# biolab_rev2.net
KiCad netlist of a schematic drawn in Altium Designer
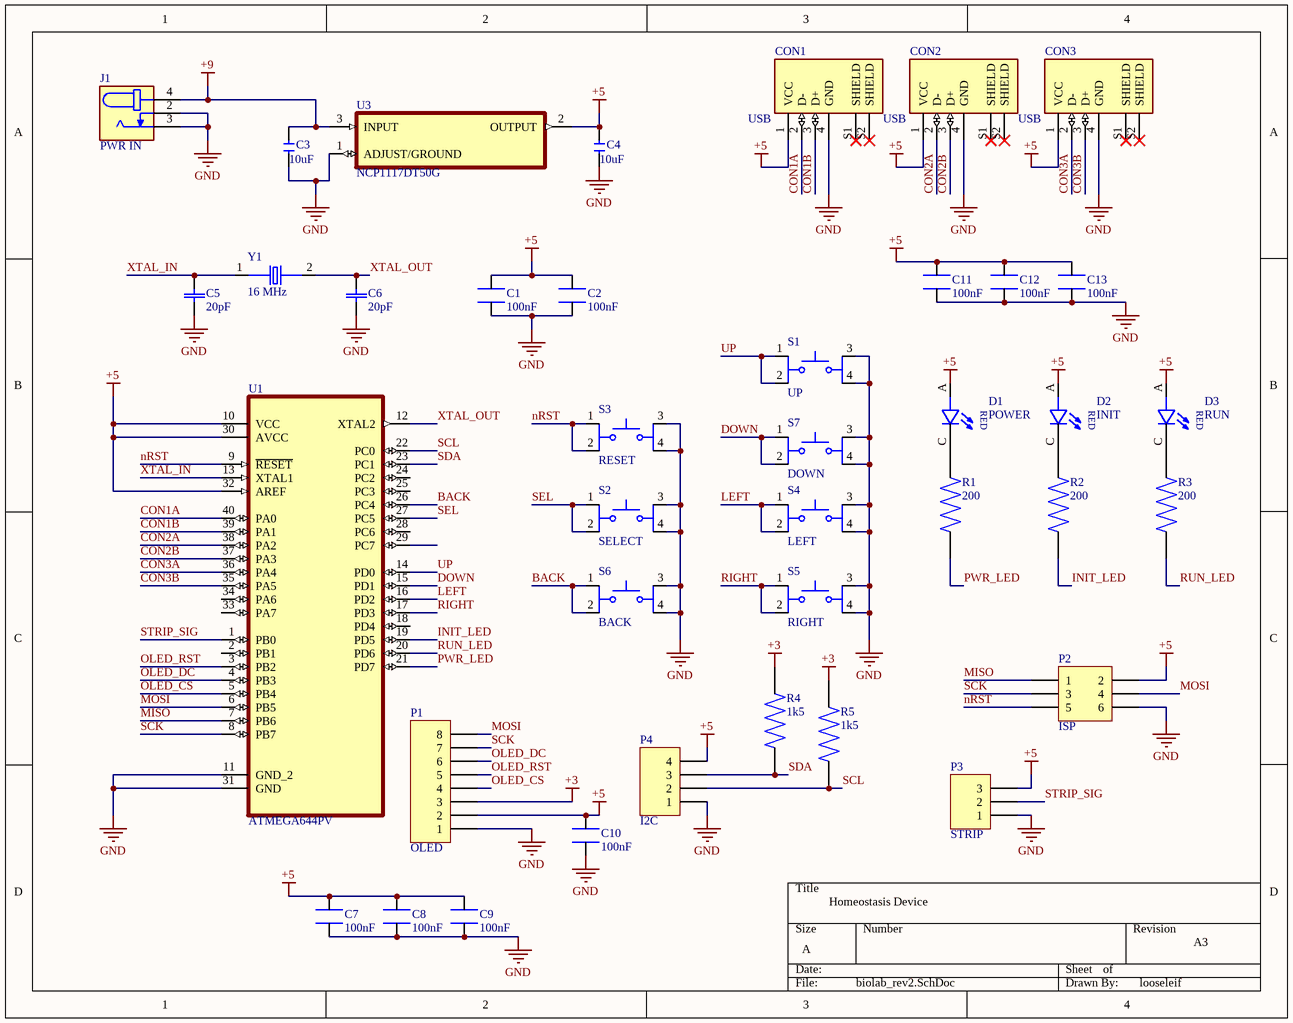
[diagram p0: biolab_rev2.SchDoc]

(export (version "E")
  (design (tool "Eeschema 10.0.6"))
  (components
    (comp (ref "C1")
      (value "100nF")
      (footprint "WCAP-CSST_885382206004")
      (fields
        (field (name "MP") "885382206004")
        (field (name "MF") "{'manufacturer': u'Wurth Electronics Inc'}")
      )
      (libsource (lib "biolab_interface") (part "885382206004"))
    )
    (comp (ref "C2")
      (value "100nF")
      (footprint "WCAP-CSST_885382206004")
      (fields
        (field (name "MP") "885382206004")
        (field (name "MF") "{'manufacturer': u'Wurth Electronics Inc'}")
      )
      (libsource (lib "biolab_interface") (part "885382206004"))
    )
    (comp (ref "C3")
      (value "10uF")
      (footprint "C0603")
      (description "302010103")
      (fields
        (field (name "MP") "CERAMIC-10UF-10V-10%-X5R(0603)")
        (field (name "MF") "{'manufacturer': u'Yageo'}")
      )
      (libsource (lib "SnapEDA_Library") (part "CERAMIC-10UF-10V-10%-X5R(0603)"))
    )
    (comp (ref "C4")
      (value "10uF")
      (footprint "C0603")
      (description "302010103")
      (fields
        (field (name "MP") "CERAMIC-10UF-10V-10%-X5R(0603)")
        (field (name "MF") "{'manufacturer': u'Yageo'}")
      )
      (libsource (lib "SnapEDA_Library") (part "CERAMIC-10UF-10V-10%-X5R(0603)"))
    )
    (comp (ref "C5")
      (value "20pF")
      (footprint "CAPC1608X85N")
      (description "CAPACITOR, 0603")
      (fields (field (name "MP") "C0603C200J5GACTU") (field (name "MF") "{'manufacturer': u'KEMET'}"))
      (libsource (lib "SnapEDA_Library") (part "C0603C200J5GACTU"))
    )
    (comp (ref "C6")
      (value "20pF")
      (footprint "CAPC1608X85N")
      (description "CAPACITOR, 0603")
      (fields (field (name "MP") "C0603C200J5GACTU") (field (name "MF") "{'manufacturer': u'KEMET'}"))
      (libsource (lib "SnapEDA_Library") (part "C0603C200J5GACTU"))
    )
    (comp (ref "C7")
      (value "100nF")
      (footprint "WCAP-CSST_885382206004")
      (fields
        (field (name "MP") "885382206004")
        (field (name "MF") "{'manufacturer': u'Wurth Electronics Inc'}")
      )
      (libsource (lib "biolab_interface") (part "885382206004"))
    )
    (comp (ref "C8")
      (value "100nF")
      (footprint "WCAP-CSST_885382206004")
      (fields
        (field (name "MP") "885382206004")
        (field (name "MF") "{'manufacturer': u'Wurth Electronics Inc'}")
      )
      (libsource (lib "biolab_interface") (part "885382206004"))
    )
    (comp (ref "C9")
      (value "100nF")
      (footprint "WCAP-CSST_885382206004")
      (fields
        (field (name "MP") "885382206004")
        (field (name "MF") "{'manufacturer': u'Wurth Electronics Inc'}")
      )
      (libsource (lib "biolab_interface") (part "885382206004"))
    )
    (comp (ref "C10")
      (value "100nF")
      (footprint "WCAP-CSST_885382206004")
      (fields
        (field (name "MP") "885382206004")
        (field (name "MF") "{'manufacturer': u'Wurth Electronics Inc'}")
      )
      (libsource (lib "biolab_interface") (part "885382206004"))
    )
    (comp (ref "C11")
      (value "100nF")
      (footprint "WCAP-CSST_885382206004")
      (fields
        (field (name "MP") "885382206004")
        (field (name "MF") "{'manufacturer': u'Wurth Electronics Inc'}")
      )
      (libsource (lib "biolab_interface") (part "885382206004"))
    )
    (comp (ref "C12")
      (value "100nF")
      (footprint "WCAP-CSST_885382206004")
      (fields
        (field (name "MP") "885382206004")
        (field (name "MF") "{'manufacturer': u'Wurth Electronics Inc'}")
      )
      (libsource (lib "biolab_interface") (part "885382206004"))
    )
    (comp (ref "C13")
      (value "100nF")
      (footprint "WCAP-CSST_885382206004")
      (fields
        (field (name "MP") "885382206004")
        (field (name "MF") "{'manufacturer': u'Wurth Electronics Inc'}")
      )
      (libsource (lib "biolab_interface") (part "885382206004"))
    )
    (comp (ref "CON1")
      (value "USB")
      (footprint "GCT_USB1130-15-A_REVA")
      (fields
        (field (name "MP") "USB1130-15-A_REVA")
        (field (name "MF") "{'manufacturer': u'Global Connector Technology'}")
      )
      (libsource (lib "SnapEDA_Library") (part "USB1130-15-A_REVA"))
    )
    (comp (ref "CON2")
      (value "USB")
      (footprint "GCT_USB1130-15-A_REVA")
      (fields
        (field (name "MP") "USB1130-15-A_REVA")
        (field (name "MF") "{'manufacturer': u'Global Connector Technology'}")
      )
      (libsource (lib "SnapEDA_Library") (part "USB1130-15-A_REVA"))
    )
    (comp (ref "CON3")
      (value "USB")
      (footprint "GCT_USB1130-15-A_REVA")
      (fields
        (field (name "MP") "USB1130-15-A_REVA")
        (field (name "MF") "{'manufacturer': u'Global Connector Technology'}")
      )
      (libsource (lib "SnapEDA_Library") (part "USB1130-15-A_REVA"))
    )
    (comp (ref "D1")
      (value "POWER")
      (footprint "LED_7012X1")
      (description "Red LED Indication - Discrete 1.7V 0805 (2012 Metric)")
      (fields (field (name "MP") "7012X1") (field (name "MF") "{'manufacturer': u'Visual'}"))
      (libsource (lib "SnapEDA_Library") (part "7012X1"))
    )
    (comp (ref "D2")
      (value "INIT")
      (footprint "LED_7012X1")
      (description "Red LED Indication - Discrete 1.7V 0805 (2012 Metric)")
      (fields (field (name "MP") "7012X1") (field (name "MF") "{'manufacturer': u'Visual'}"))
      (libsource (lib "SnapEDA_Library") (part "7012X1"))
    )
    (comp (ref "D3")
      (value "RUN")
      (footprint "LED_7012X1")
      (description "Red LED Indication - Discrete 1.7V 0805 (2012 Metric)")
      (fields (field (name "MP") "7012X1") (field (name "MF") "{'manufacturer': u'Visual'}"))
      (libsource (lib "SnapEDA_Library") (part "7012X1"))
    )
    (comp (ref "J1")
      (value "PWR IN")
      (footprint "NINIGI_DC-005")
      (description "DC Jack")
      (fields (field (name "MP") "DC-005") (field (name "MF") "{'manufacturer': u'Best Inc.'}"))
      (libsource (lib "SnapEDA_Library") (part "DC-005"))
    )
    (comp (ref "P1")
      (value "OLED")
      (footprint "HDR1X8")
      (description "Header, 8-Pin")
      (fields (field (name "PUBLISHER") "Altium Limited"))
      (libsource (lib "Miscellaneous Connectors") (part "Header 8"))
    )
    (comp (ref "P2")
      (value "ISP")
      (footprint "HDR2X3")
      (description "Header, 3-Pin, Dual row")
      (fields (field (name "PUBLISHER") "Altium Limited"))
      (libsource (lib "Miscellaneous Connectors") (part "Header 3X2"))
    )
    (comp (ref "P3")
      (value "STRIP")
      (footprint "HDR1X3H")
      (description "Header, 3-Pin, Right Angle")
      (fields (field (name "PUBLISHER") "Altium Limited"))
      (libsource (lib "Miscellaneous Connectors") (part "Header 3H"))
    )
    (comp (ref "P4")
      (value "I2C")
      (footprint "HDR1X4H")
      (description "Header, 4-Pin, Right Angle")
      (fields (field (name "PUBLISHER") "Altium Limited"))
      (libsource (lib "Miscellaneous Connectors") (part "Header 4H"))
    )
    (comp (ref "R1")
      (value "200")
      (footprint "RESC1608X55N")
      (fields (field (name "MP") "SR0603JR-07200RL") (field (name "MF") "{'manufacturer': u'Yageo'}"))
      (libsource (lib "biolab_interface") (part "SR0603JR-07200RL"))
    )
    (comp (ref "R2")
      (value "200")
      (footprint "RESC1608X55N")
      (fields (field (name "MP") "SR0603JR-07200RL") (field (name "MF") "{'manufacturer': u'Yageo'}"))
      (libsource (lib "biolab_interface") (part "SR0603JR-07200RL"))
    )
    (comp (ref "R3")
      (value "200")
      (footprint "RESC1608X55N")
      (fields (field (name "MP") "SR0603JR-07200RL") (field (name "MF") "{'manufacturer': u'Yageo'}"))
      (libsource (lib "biolab_interface") (part "SR0603JR-07200RL"))
    )
    (comp (ref "R4")
      (value "1k5")
      (footprint "RESC1508X55N")
      (fields (field (name "MP") "TNPW06031K50BXEN") (field (name "MF") "{'manufacturer': u'Vishay'}"))
      (libsource (lib "biolab_interface") (part "TNPW06031K50BXEN"))
    )
    (comp (ref "R5")
      (value "1k5")
      (footprint "RESC1508X55N")
      (fields (field (name "MP") "TNPW06031K50BXEN") (field (name "MF") "{'manufacturer': u'Vishay'}"))
      (libsource (lib "biolab_interface") (part "TNPW06031K50BXEN"))
    )
    (comp (ref "S1")
      (value "UP")
      (footprint "SW_TL3301AF160QG")
      (fields (field (name "MP") "TL3301AF160QG") (field (name "MF") "{'manufacturer': u'E-Switch'}"))
      (libsource (lib "biolab_interface") (part "TL3301AF160QG"))
    )
    (comp (ref "S2")
      (value "SELECT")
      (footprint "SW_TL3301AF160QG")
      (fields (field (name "MP") "TL3301AF160QG") (field (name "MF") "{'manufacturer': u'E-Switch'}"))
      (libsource (lib "biolab_interface") (part "TL3301AF160QG"))
    )
    (comp (ref "S3")
      (value "RESET")
      (footprint "SW_TL3301AF160QG")
      (fields (field (name "MP") "TL3301AF160QG") (field (name "MF") "{'manufacturer': u'E-Switch'}"))
      (libsource (lib "biolab_interface") (part "TL3301AF160QG"))
    )
    (comp (ref "S4")
      (value "LEFT")
      (footprint "SW_TL3301AF160QG")
      (fields (field (name "MP") "TL3301AF160QG") (field (name "MF") "{'manufacturer': u'E-Switch'}"))
      (libsource (lib "biolab_interface") (part "TL3301AF160QG"))
    )
    (comp (ref "S5")
      (value "RIGHT")
      (footprint "SW_TL3301AF160QG")
      (fields (field (name "MP") "TL3301AF160QG") (field (name "MF") "{'manufacturer': u'E-Switch'}"))
      (libsource (lib "biolab_interface") (part "TL3301AF160QG"))
    )
    (comp (ref "S6")
      (value "BACK")
      (footprint "SW_TL3301AF160QG")
      (fields (field (name "MP") "TL3301AF160QG") (field (name "MF") "{'manufacturer': u'E-Switch'}"))
      (libsource (lib "biolab_interface") (part "TL3301AF160QG"))
    )
    (comp (ref "S7")
      (value "DOWN")
      (footprint "SW_TL3301AF160QG")
      (fields (field (name "MP") "TL3301AF160QG") (field (name "MF") "{'manufacturer': u'E-Switch'}"))
      (libsource (lib "biolab_interface") (part "TL3301AF160QG"))
    )
    (comp (ref "U1")
      (value "ATMEGA644PV")
      (footprint "DIP254P1524X483-40")
      (description "8-bit Microcontroller with In-System Programmable  Flash")
      (fields
        (field (name "MP") "ATMEGA644PV-10PU")
        (field (name "MF") "{'manufacturer': u'Microchip Technology'}")
      )
      (libsource (lib "SnapEDA_Library") (part "ATMEGA644PV-10PU"))
    )
    (comp (ref "U3")
      (value "NCP1117DT50G")
      (footprint "DPAK229P990X238-4N")
      (fields (field (name "MF") "{'manufacturer': u'ON Semiconductor'}"))
      (libsource (lib "SnapEDA_Library") (part "NCP1117DT50G"))
    )
    (comp (ref "Y1")
      (value "16 MHz")
      (footprint "XTAL_FOXSDLF/160-20")
      (description "Crystal 16MHz 20pF 2-Pin HC-49/SD")
      (fields (field (name "MP") "FOXSDLF/160-20") (field (name "MF") "{'manufacturer': u'Fox Electronics'}"))
      (libsource (lib "SnapEDA_Library") (part "FOXSDLF/160-20"))
    )
  )
  (nets
    (net (code "1") (name "+3") (class "Default")
      (node (ref "P1") (pin "3") (pinfunction "3_3") (pintype "passive"))
      (node (ref "R4") (pin "2") (pinfunction "2_2") (pintype "passive"))
      (node (ref "R5") (pin "2") (pinfunction "2_2") (pintype "passive"))
    )
    (net (code "2") (name "+5") (class "Default")
      (node (ref "C1") (pin "2") (pinfunction "2_2") (pintype "passive"))
      (node (ref "C10") (pin "2") (pinfunction "2_2") (pintype "passive"))
      (node (ref "C11") (pin "2") (pinfunction "2_2") (pintype "passive"))
      (node (ref "C12") (pin "2") (pinfunction "2_2") (pintype "passive"))
      (node (ref "C13") (pin "2") (pinfunction "2_2") (pintype "passive"))
      (node (ref "C2") (pin "2") (pinfunction "2_2") (pintype "passive"))
      (node (ref "C4") (pin "2") (pinfunction "2_2") (pintype "passive"))
      (node (ref "C7") (pin "2") (pinfunction "2_2") (pintype "passive"))
      (node (ref "C8") (pin "2") (pinfunction "2_2") (pintype "passive"))
      (node (ref "C9") (pin "2") (pinfunction "2_2") (pintype "passive"))
      (node (ref "CON1") (pin "1") (pinfunction "VCC_1") (pintype "power_in"))
      (node (ref "CON2") (pin "1") (pinfunction "VCC_1") (pintype "power_in"))
      (node (ref "CON3") (pin "1") (pinfunction "VCC_1") (pintype "power_in"))
      (node (ref "D1") (pin "A") (pinfunction "A_A") (pintype "passive"))
      (node (ref "D2") (pin "A") (pinfunction "A_A") (pintype "passive"))
      (node (ref "D3") (pin "A") (pinfunction "A_A") (pintype "passive"))
      (node (ref "P1") (pin "2") (pinfunction "2_2") (pintype "passive"))
      (node (ref "P2") (pin "2") (pinfunction "2_2") (pintype "passive"))
      (node (ref "P3") (pin "3") (pinfunction "3_3") (pintype "passive"))
      (node (ref "P4") (pin "4") (pinfunction "4_4") (pintype "passive"))
      (node (ref "U1") (pin "10") (pinfunction "VCC_10") (pintype "power_in"))
      (node (ref "U1") (pin "30") (pinfunction "AVCC_30") (pintype "power_in"))
      (node (ref "U1") (pin "32") (pinfunction "AREF_32") (pintype "input"))
      (node (ref "U3") (pin "2") (pinfunction "OUTPUT_2") (pintype "output"))
    )
    (net (code "3") (name "+9") (class "Default")
      (node (ref "C3") (pin "2") (pinfunction "2_2") (pintype "passive"))
      (node (ref "J1") (pin "4") (pinfunction "2_4") (pintype "passive"))
      (node (ref "U3") (pin "3") (pinfunction "INPUT_3") (pintype "input"))
    )
    (net (code "4") (name "/BACK") (class "Default")
      (node (ref "S6") (pin "1") (pinfunction "1_1") (pintype "passive"))
      (node (ref "S6") (pin "2") (pinfunction "2_2") (pintype "passive"))
      (node (ref "U1") (pin "26") (pinfunction "PC4_26") (pintype "bidirectional"))
    )
    (net (code "5") (name "/CON1A") (class "Default")
      (node (ref "CON1") (pin "2") (pinfunction "D-_2") (pintype "bidirectional"))
      (node (ref "U1") (pin "40") (pinfunction "PA0_40") (pintype "bidirectional"))
    )
    (net (code "6") (name "/CON1B") (class "Default")
      (node (ref "CON1") (pin "3") (pinfunction "D+_3") (pintype "bidirectional"))
      (node (ref "U1") (pin "39") (pinfunction "PA1_39") (pintype "bidirectional"))
    )
    (net (code "7") (name "/CON2A") (class "Default")
      (node (ref "CON2") (pin "2") (pinfunction "D-_2") (pintype "bidirectional"))
      (node (ref "U1") (pin "38") (pinfunction "PA2_38") (pintype "bidirectional"))
    )
    (net (code "8") (name "/CON2B") (class "Default")
      (node (ref "CON2") (pin "3") (pinfunction "D+_3") (pintype "bidirectional"))
      (node (ref "U1") (pin "37") (pinfunction "PA3_37") (pintype "bidirectional"))
    )
    (net (code "9") (name "/CON3A") (class "Default")
      (node (ref "CON3") (pin "2") (pinfunction "D-_2") (pintype "bidirectional"))
      (node (ref "U1") (pin "36") (pinfunction "PA4_36") (pintype "bidirectional"))
    )
    (net (code "10") (name "/CON3B") (class "Default")
      (node (ref "CON3") (pin "3") (pinfunction "D+_3") (pintype "bidirectional"))
      (node (ref "U1") (pin "35") (pinfunction "PA5_35") (pintype "bidirectional"))
    )
    (net (code "11") (name "/DOWN") (class "Default")
      (node (ref "S7") (pin "1") (pinfunction "1_1") (pintype "passive"))
      (node (ref "S7") (pin "2") (pinfunction "2_2") (pintype "passive"))
      (node (ref "U1") (pin "15") (pinfunction "PD1_15") (pintype "bidirectional"))
    )
    (net (code "12") (name "/INIT_LED") (class "Default")
      (node (ref "R2") (pin "1") (pinfunction "1_1") (pintype "passive"))
      (node (ref "U1") (pin "19") (pinfunction "PD5_19") (pintype "bidirectional"))
    )
    (net (code "13") (name "/LEFT") (class "Default")
      (node (ref "S4") (pin "1") (pinfunction "1_1") (pintype "passive"))
      (node (ref "S4") (pin "2") (pinfunction "2_2") (pintype "passive"))
      (node (ref "U1") (pin "16") (pinfunction "PD2_16") (pintype "bidirectional"))
    )
    (net (code "14") (name "/MISO") (class "Default")
      (node (ref "P2") (pin "1") (pinfunction "1_1") (pintype "passive"))
      (node (ref "U1") (pin "7") (pinfunction "PB6_7") (pintype "bidirectional"))
    )
    (net (code "15") (name "/MOSI") (class "Default")
      (node (ref "P1") (pin "8") (pinfunction "8_8") (pintype "passive"))
      (node (ref "P2") (pin "4") (pinfunction "4_4") (pintype "passive"))
      (node (ref "U1") (pin "6") (pinfunction "PB5_6") (pintype "bidirectional"))
    )
    (net (code "16") (name "/OLED_CS") (class "Default")
      (node (ref "P1") (pin "4") (pinfunction "4_4") (pintype "passive"))
      (node (ref "U1") (pin "5") (pinfunction "PB4_5") (pintype "bidirectional"))
    )
    (net (code "17") (name "/OLED_DC") (class "Default")
      (node (ref "P1") (pin "6") (pinfunction "6_6") (pintype "passive"))
      (node (ref "U1") (pin "4") (pinfunction "PB3_4") (pintype "bidirectional"))
    )
    (net (code "18") (name "/OLED_RST") (class "Default")
      (node (ref "P1") (pin "5") (pinfunction "5_5") (pintype "passive"))
      (node (ref "U1") (pin "3") (pinfunction "PB2_3") (pintype "bidirectional"))
    )
    (net (code "19") (name "/PWR_LED") (class "Default")
      (node (ref "R1") (pin "1") (pinfunction "1_1") (pintype "passive"))
      (node (ref "U1") (pin "21") (pinfunction "PD7_21") (pintype "bidirectional"))
    )
    (net (code "20") (name "/RIGHT") (class "Default")
      (node (ref "S5") (pin "1") (pinfunction "1_1") (pintype "passive"))
      (node (ref "S5") (pin "2") (pinfunction "2_2") (pintype "passive"))
      (node (ref "U1") (pin "17") (pinfunction "PD3_17") (pintype "bidirectional"))
    )
    (net (code "21") (name "/RUN_LED") (class "Default")
      (node (ref "R3") (pin "1") (pinfunction "1_1") (pintype "passive"))
      (node (ref "U1") (pin "20") (pinfunction "PD6_20") (pintype "bidirectional"))
    )
    (net (code "22") (name "/SCK") (class "Default")
      (node (ref "P1") (pin "7") (pinfunction "7_7") (pintype "passive"))
      (node (ref "P2") (pin "3") (pinfunction "3_3") (pintype "passive"))
      (node (ref "U1") (pin "8") (pinfunction "PB7_8") (pintype "bidirectional"))
    )
    (net (code "23") (name "/SCL") (class "Default")
      (node (ref "P4") (pin "2") (pinfunction "2_2") (pintype "passive"))
      (node (ref "R5") (pin "1") (pinfunction "1_1") (pintype "passive"))
      (node (ref "U1") (pin "22") (pinfunction "PC0_22") (pintype "bidirectional"))
    )
    (net (code "24") (name "/SDA") (class "Default")
      (node (ref "P4") (pin "3") (pinfunction "3_3") (pintype "passive"))
      (node (ref "R4") (pin "1") (pinfunction "1_1") (pintype "passive"))
      (node (ref "U1") (pin "23") (pinfunction "PC1_23") (pintype "bidirectional"))
    )
    (net (code "25") (name "/SEL") (class "Default")
      (node (ref "S2") (pin "1") (pinfunction "1_1") (pintype "passive"))
      (node (ref "S2") (pin "2") (pinfunction "2_2") (pintype "passive"))
      (node (ref "U1") (pin "27") (pinfunction "PC5_27") (pintype "bidirectional"))
    )
    (net (code "26") (name "/STRIP_SIG") (class "Default")
      (node (ref "P3") (pin "2") (pinfunction "2_2") (pintype "passive"))
      (node (ref "U1") (pin "1") (pinfunction "PB0_1") (pintype "bidirectional"))
    )
    (net (code "27") (name "/UP") (class "Default")
      (node (ref "S1") (pin "1") (pinfunction "1_1") (pintype "passive"))
      (node (ref "S1") (pin "2") (pinfunction "2_2") (pintype "passive"))
      (node (ref "U1") (pin "14") (pinfunction "PD0_14") (pintype "bidirectional"))
    )
    (net (code "28") (name "/XTAL_IN") (class "Default")
      (node (ref "C5") (pin "2") (pinfunction "C2_2") (pintype "passive"))
      (node (ref "U1") (pin "13") (pinfunction "XTAL1_13") (pintype "input"))
      (node (ref "Y1") (pin "1") (pinfunction "1_1") (pintype "passive"))
    )
    (net (code "29") (name "/XTAL_OUT") (class "Default")
      (node (ref "C6") (pin "2") (pinfunction "C2_2") (pintype "passive"))
      (node (ref "U1") (pin "12") (pinfunction "XTAL2_12") (pintype "output"))
      (node (ref "Y1") (pin "2") (pinfunction "2_2") (pintype "passive"))
    )
    (net (code "30") (name "/nRST") (class "Default")
      (node (ref "P2") (pin "5") (pinfunction "5_5") (pintype "passive"))
      (node (ref "S3") (pin "1") (pinfunction "1_1") (pintype "passive"))
      (node (ref "S3") (pin "2") (pinfunction "2_2") (pintype "passive"))
      (node (ref "U1") (pin "9") (pinfunction "~{RESET}_9") (pintype "input"))
    )
    (net (code "31") (name "GND") (class "Default")
      (node (ref "C1") (pin "1") (pinfunction "1_1") (pintype "passive"))
      (node (ref "C10") (pin "1") (pinfunction "1_1") (pintype "passive"))
      (node (ref "C11") (pin "1") (pinfunction "1_1") (pintype "passive"))
      (node (ref "C12") (pin "1") (pinfunction "1_1") (pintype "passive"))
      (node (ref "C13") (pin "1") (pinfunction "1_1") (pintype "passive"))
      (node (ref "C2") (pin "1") (pinfunction "1_1") (pintype "passive"))
      (node (ref "C3") (pin "1") (pinfunction "1_1") (pintype "passive"))
      (node (ref "C4") (pin "1") (pinfunction "1_1") (pintype "passive"))
      (node (ref "C5") (pin "1") (pinfunction "C1_1") (pintype "passive"))
      (node (ref "C6") (pin "1") (pinfunction "C1_1") (pintype "passive"))
      (node (ref "C7") (pin "1") (pinfunction "1_1") (pintype "passive"))
      (node (ref "C8") (pin "1") (pinfunction "1_1") (pintype "passive"))
      (node (ref "C9") (pin "1") (pinfunction "1_1") (pintype "passive"))
      (node (ref "CON1") (pin "4") (pinfunction "GND_4") (pintype "power_in"))
      (node (ref "CON2") (pin "4") (pinfunction "GND_4") (pintype "power_in"))
      (node (ref "CON3") (pin "4") (pinfunction "GND_4") (pintype "power_in"))
      (node (ref "J1") (pin "2") (pinfunction "4_2") (pintype "passive"))
      (node (ref "J1") (pin "3") (pinfunction "5_3") (pintype "passive"))
      (node (ref "P1") (pin "1") (pinfunction "1_1") (pintype "passive"))
      (node (ref "P2") (pin "6") (pinfunction "6_6") (pintype "passive"))
      (node (ref "P3") (pin "1") (pinfunction "1_1") (pintype "passive"))
      (node (ref "P4") (pin "1") (pinfunction "1_1") (pintype "passive"))
      (node (ref "S1") (pin "3") (pinfunction "3_3") (pintype "passive"))
      (node (ref "S1") (pin "4") (pinfunction "4_4") (pintype "passive"))
      (node (ref "S2") (pin "3") (pinfunction "3_3") (pintype "passive"))
      (node (ref "S2") (pin "4") (pinfunction "4_4") (pintype "passive"))
      (node (ref "S3") (pin "3") (pinfunction "3_3") (pintype "passive"))
      (node (ref "S3") (pin "4") (pinfunction "4_4") (pintype "passive"))
      (node (ref "S4") (pin "3") (pinfunction "3_3") (pintype "passive"))
      (node (ref "S4") (pin "4") (pinfunction "4_4") (pintype "passive"))
      (node (ref "S5") (pin "3") (pinfunction "3_3") (pintype "passive"))
      (node (ref "S5") (pin "4") (pinfunction "4_4") (pintype "passive"))
      (node (ref "S6") (pin "3") (pinfunction "3_3") (pintype "passive"))
      (node (ref "S6") (pin "4") (pinfunction "4_4") (pintype "passive"))
      (node (ref "S7") (pin "3") (pinfunction "3_3") (pintype "passive"))
      (node (ref "S7") (pin "4") (pinfunction "4_4") (pintype "passive"))
      (node (ref "U1") (pin "11") (pinfunction "GND_2_11") (pintype "passive"))
      (node (ref "U1") (pin "31") (pinfunction "GND_31") (pintype "passive"))
      (node (ref "U3") (pin "1") (pinfunction "ADJUST/GROUND_1") (pintype "bidirectional"))
    )
    (net (code "32") (name "Net-(D1-PadC)") (class "Default")
      (node (ref "D1") (pin "C") (pinfunction "C_C") (pintype "passive"))
      (node (ref "R1") (pin "2") (pinfunction "2_2") (pintype "passive"))
    )
    (net (code "33") (name "Net-(D2-PadC)") (class "Default")
      (node (ref "D2") (pin "C") (pinfunction "C_C") (pintype "passive"))
      (node (ref "R2") (pin "2") (pinfunction "2_2") (pintype "passive"))
    )
    (net (code "34") (name "Net-(D3-PadC)") (class "Default")
      (node (ref "D3") (pin "C") (pinfunction "C_C") (pintype "passive"))
      (node (ref "R3") (pin "2") (pinfunction "2_2") (pintype "passive"))
    )
    (net (code "35") (name "unconnected-(CON1-SHIELD-PadS1)") (class "Default")
      (node (ref "CON1") (pin "S1") (pinfunction "SHIELD_S1") (pintype "passive+no_connect"))
    )
    (net (code "36") (name "unconnected-(CON1-SHIELD-PadS2)") (class "Default")
      (node (ref "CON1") (pin "S2") (pinfunction "SHIELD_S2") (pintype "passive+no_connect"))
    )
    (net (code "37") (name "unconnected-(CON2-SHIELD-PadS1)") (class "Default")
      (node (ref "CON2") (pin "S1") (pinfunction "SHIELD_S1") (pintype "passive+no_connect"))
    )
    (net (code "38") (name "unconnected-(CON2-SHIELD-PadS2)") (class "Default")
      (node (ref "CON2") (pin "S2") (pinfunction "SHIELD_S2") (pintype "passive+no_connect"))
    )
    (net (code "39") (name "unconnected-(CON3-SHIELD-PadS1)") (class "Default")
      (node (ref "CON3") (pin "S1") (pinfunction "SHIELD_S1") (pintype "passive+no_connect"))
    )
    (net (code "40") (name "unconnected-(CON3-SHIELD-PadS2)") (class "Default")
      (node (ref "CON3") (pin "S2") (pinfunction "SHIELD_S2") (pintype "passive+no_connect"))
    )
    (net (code "41") (name "unconnected-(U1-PA6-Pad34)") (class "Default")
      (node (ref "U1") (pin "34") (pinfunction "PA6_34") (pintype "bidirectional"))
    )
    (net (code "42") (name "unconnected-(U1-PA7-Pad33)") (class "Default")
      (node (ref "U1") (pin "33") (pinfunction "PA7_33") (pintype "bidirectional"))
    )
    (net (code "43") (name "unconnected-(U1-PB1-Pad2)") (class "Default")
      (node (ref "U1") (pin "2") (pinfunction "PB1_2") (pintype "bidirectional"))
    )
    (net (code "44") (name "unconnected-(U1-PC2-Pad24)") (class "Default")
      (node (ref "U1") (pin "24") (pinfunction "PC2_24") (pintype "bidirectional"))
    )
    (net (code "45") (name "unconnected-(U1-PC3-Pad25)") (class "Default")
      (node (ref "U1") (pin "25") (pinfunction "PC3_25") (pintype "bidirectional"))
    )
    (net (code "46") (name "unconnected-(U1-PC6-Pad28)") (class "Default")
      (node (ref "U1") (pin "28") (pinfunction "PC6_28") (pintype "bidirectional"))
    )
    (net (code "47") (name "unconnected-(U1-PC7-Pad29)") (class "Default")
      (node (ref "U1") (pin "29") (pinfunction "PC7_29") (pintype "bidirectional"))
    )
    (net (code "48") (name "unconnected-(U1-PD4-Pad18)") (class "Default")
      (node (ref "U1") (pin "18") (pinfunction "PD4_18") (pintype "bidirectional"))
    )
  )
)
